# Sensor_Acquisition_Board_Rev1.net
KiCad netlist of a schematic drawn in EAGLE
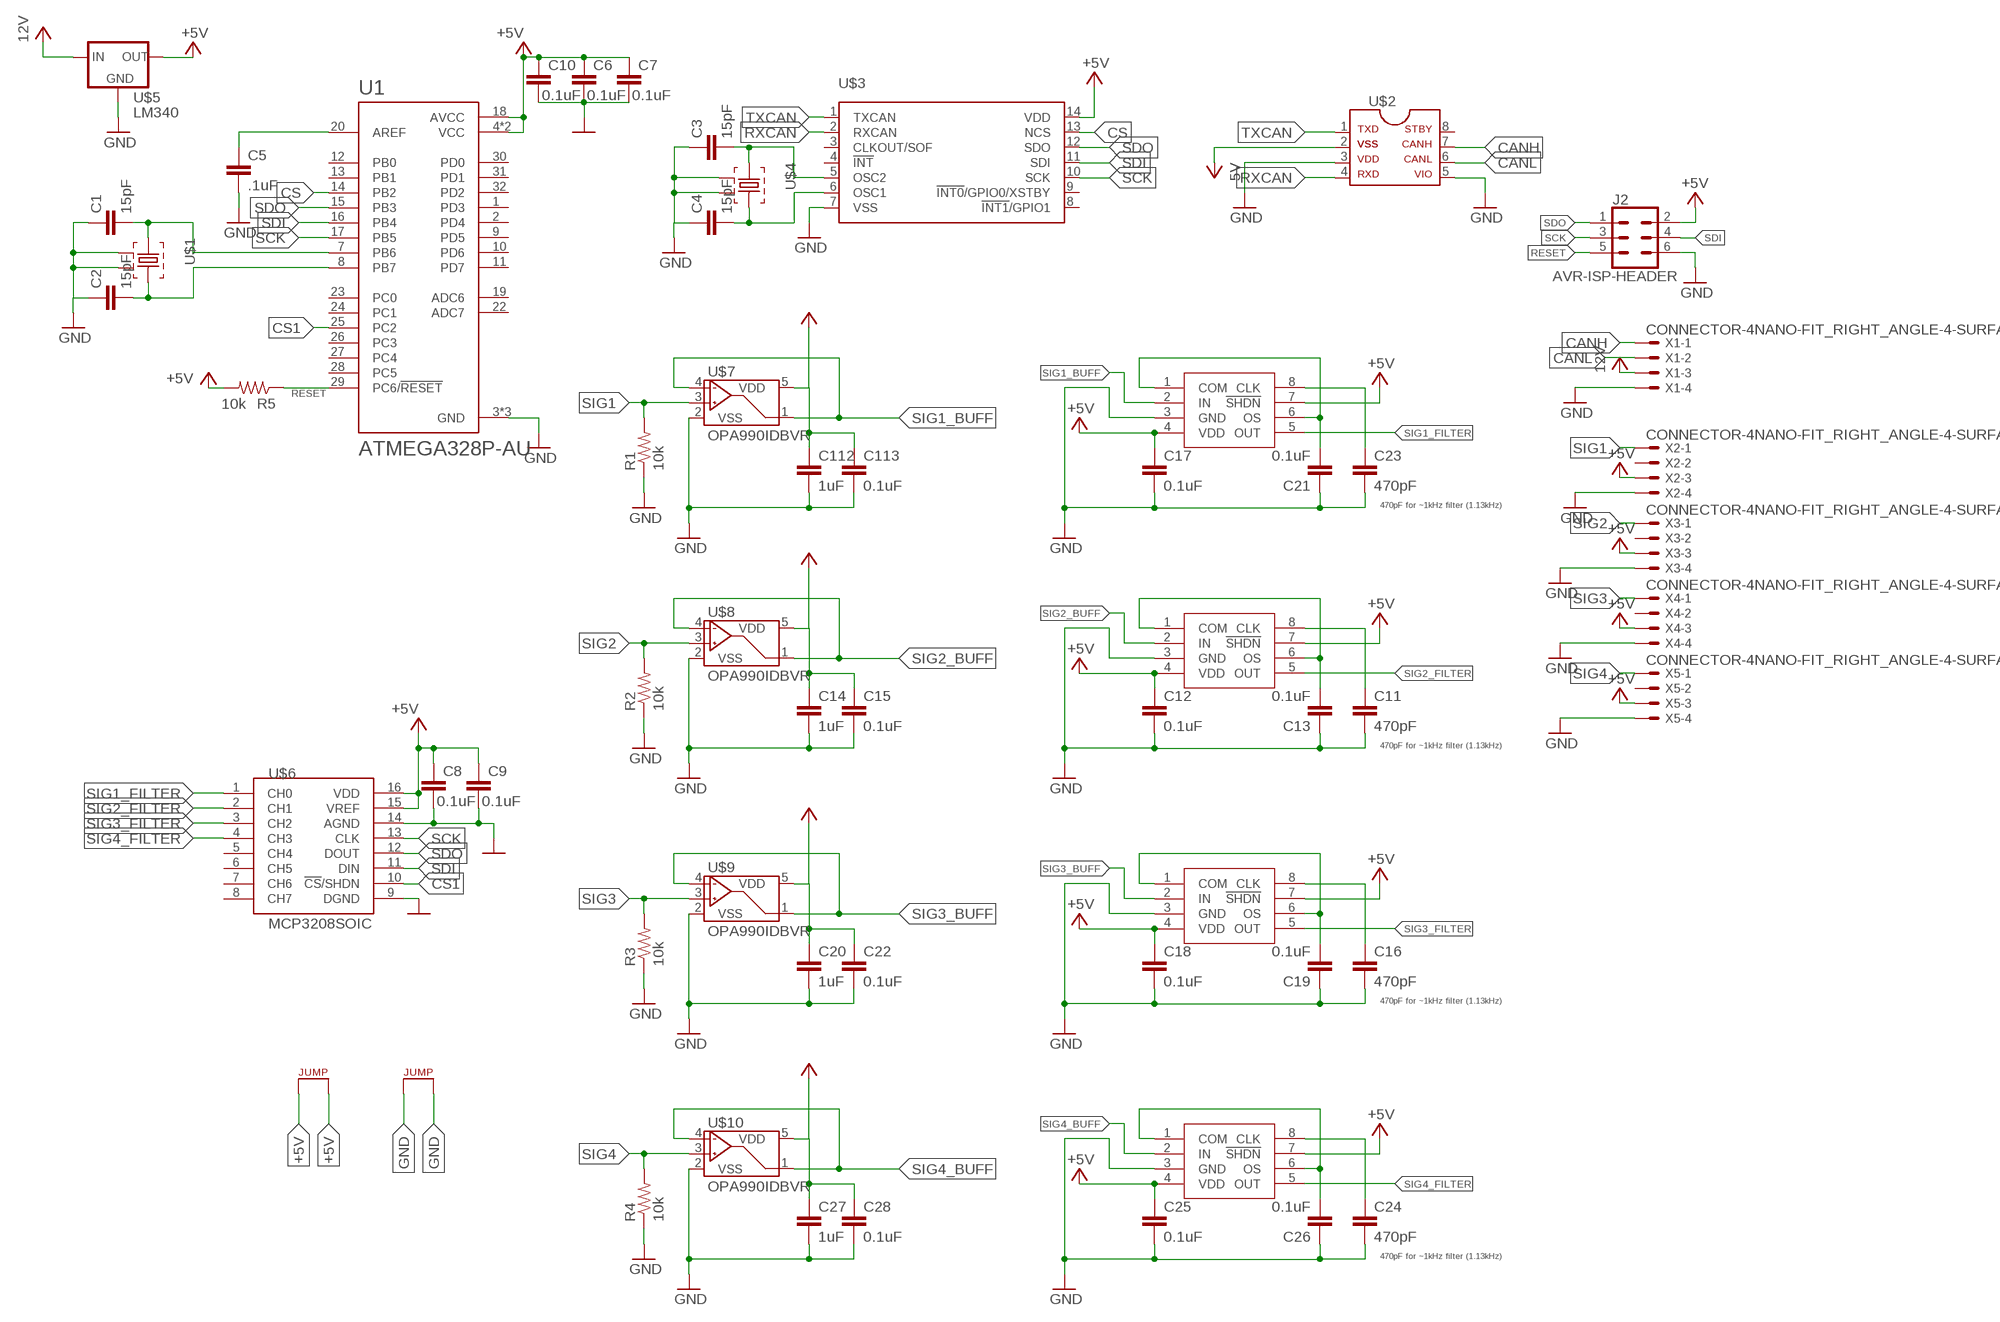
[diagram p0: schematic, sheet 1]

(export (version "E")
  (design (tool "Eeschema 10.0.6"))
  (components
    (comp (ref "C1")
      (value "15pF")
      (footprint "eagle-import:0603-CAP")
      (libsource (lib "eagle-import") (part "CAP0603-CAP"))
    )
    (comp (ref "C2")
      (value "15pF")
      (footprint "eagle-import:0603-CAP")
      (libsource (lib "eagle-import") (part "CAP0603-CAP"))
    )
    (comp (ref "C3")
      (value "15pF")
      (footprint "eagle-import:0603-CAP")
      (libsource (lib "eagle-import") (part "CAP0603-CAP"))
    )
    (comp (ref "C4")
      (value "15pF")
      (footprint "eagle-import:0603-CAP")
      (libsource (lib "eagle-import") (part "CAP0603-CAP"))
    )
    (comp (ref "C5")
      (value ".1uF")
      (footprint "eagle-import:0603-CAP")
      (libsource (lib "eagle-import") (part "CAP0603-CAP"))
    )
    (comp (ref "C6")
      (value "0.1uF")
      (footprint "eagle-import:0603-CAP")
      (libsource (lib "eagle-import") (part "CAP0603-CAP"))
    )
    (comp (ref "C7")
      (value "0.1uF")
      (footprint "eagle-import:0603-CAP")
      (libsource (lib "eagle-import") (part "CAP0603-CAP"))
    )
    (comp (ref "C8")
      (value "0.1uF")
      (footprint "eagle-import:0603-CAP")
      (libsource (lib "eagle-import") (part "CAP0603-CAP"))
    )
    (comp (ref "C9")
      (value "0.1uF")
      (footprint "eagle-import:0603-CAP")
      (libsource (lib "eagle-import") (part "CAP0603-CAP"))
    )
    (comp (ref "C10")
      (value "0.1uF")
      (footprint "eagle-import:0603-CAP")
      (libsource (lib "eagle-import") (part "CAP0603-CAP"))
    )
    (comp (ref "C11")
      (value "470pF")
      (footprint "eagle-import:0603-CAP")
      (libsource (lib "eagle-import") (part "CAP0603-CAP"))
    )
    (comp (ref "C12")
      (value "0.1uF")
      (footprint "eagle-import:0603-CAP")
      (libsource (lib "eagle-import") (part "CAP0603-CAP"))
    )
    (comp (ref "C13")
      (value "0.1uF")
      (footprint "eagle-import:0603-CAP")
      (libsource (lib "eagle-import") (part "CAP0603-CAP"))
    )
    (comp (ref "C14")
      (value "1uF")
      (footprint "eagle-import:0603-CAP")
      (libsource (lib "eagle-import") (part "CAP0603-CAP"))
    )
    (comp (ref "C15")
      (value "0.1uF")
      (footprint "eagle-import:0603-CAP")
      (libsource (lib "eagle-import") (part "CAP0603-CAP"))
    )
    (comp (ref "C16")
      (value "470pF")
      (footprint "eagle-import:0603-CAP")
      (libsource (lib "eagle-import") (part "CAP0603-CAP"))
    )
    (comp (ref "C17")
      (value "0.1uF")
      (footprint "eagle-import:0603-CAP")
      (libsource (lib "eagle-import") (part "CAP0603-CAP"))
    )
    (comp (ref "C18")
      (value "0.1uF")
      (footprint "eagle-import:0603-CAP")
      (libsource (lib "eagle-import") (part "CAP0603-CAP"))
    )
    (comp (ref "C19")
      (value "0.1uF")
      (footprint "eagle-import:0603-CAP")
      (libsource (lib "eagle-import") (part "CAP0603-CAP"))
    )
    (comp (ref "C20")
      (value "1uF")
      (footprint "eagle-import:0603-CAP")
      (libsource (lib "eagle-import") (part "CAP0603-CAP"))
    )
    (comp (ref "C21")
      (value "0.1uF")
      (footprint "eagle-import:0603-CAP")
      (libsource (lib "eagle-import") (part "CAP0603-CAP"))
    )
    (comp (ref "C22")
      (value "0.1uF")
      (footprint "eagle-import:0603-CAP")
      (libsource (lib "eagle-import") (part "CAP0603-CAP"))
    )
    (comp (ref "C23")
      (value "470pF")
      (footprint "eagle-import:0603-CAP")
      (libsource (lib "eagle-import") (part "CAP0603-CAP"))
    )
    (comp (ref "C24")
      (value "470pF")
      (footprint "eagle-import:0603-CAP")
      (libsource (lib "eagle-import") (part "CAP0603-CAP"))
    )
    (comp (ref "C25")
      (value "0.1uF")
      (footprint "eagle-import:0603-CAP")
      (libsource (lib "eagle-import") (part "CAP0603-CAP"))
    )
    (comp (ref "C26")
      (value "0.1uF")
      (footprint "eagle-import:0603-CAP")
      (libsource (lib "eagle-import") (part "CAP0603-CAP"))
    )
    (comp (ref "C27")
      (value "1uF")
      (footprint "eagle-import:0603-CAP")
      (libsource (lib "eagle-import") (part "CAP0603-CAP"))
    )
    (comp (ref "C28")
      (value "0.1uF")
      (footprint "eagle-import:0603-CAP")
      (libsource (lib "eagle-import") (part "CAP0603-CAP"))
    )
    (comp (ref "C112")
      (value "1uF")
      (footprint "eagle-import:0603-CAP")
      (libsource (lib "eagle-import") (part "CAP0603-CAP"))
    )
    (comp (ref "C113")
      (value "0.1uF")
      (footprint "eagle-import:0603-CAP")
      (libsource (lib "eagle-import") (part "CAP0603-CAP"))
    )
    (comp (ref "J1")
      (value "JUMPER.1")
      (footprint "eagle-import:1X02")
      (libsource (lib "eagle-import") (part "JUMPER.1"))
    )
    (comp (ref "J2")
      (value "AVR-ISP-HEADER")
      (footprint "eagle-import:2X03")
      (libsource (lib "eagle-import") (part "AVR-ISP-HEADER"))
    )
    (comp (ref "J3")
      (value "JUMPER.1")
      (footprint "eagle-import:1X02")
      (libsource (lib "eagle-import") (part "JUMPER.1"))
    )
    (comp (ref "R1")
      (value "10k")
      (footprint "eagle-import:0603-RES")
      (libsource (lib "eagle-import") (part "RESISTOR0603"))
    )
    (comp (ref "R2")
      (value "10k")
      (footprint "eagle-import:0603-RES")
      (libsource (lib "eagle-import") (part "RESISTOR0603"))
    )
    (comp (ref "R3")
      (value "10k")
      (footprint "eagle-import:0603-RES")
      (libsource (lib "eagle-import") (part "RESISTOR0603"))
    )
    (comp (ref "R4")
      (value "10k")
      (footprint "eagle-import:0603-RES")
      (libsource (lib "eagle-import") (part "RESISTOR0603"))
    )
    (comp (ref "R5")
      (value "10k")
      (footprint "eagle-import:0603-RES")
      (libsource (lib "eagle-import") (part "RESISTOR0603"))
    )
    (comp (ref "U$1")
      (value "ABM3B")
      (footprint "eagle-import:ABM3B")
      (libsource (lib "eagle-import") (part "ABM3B"))
    )
    (comp (ref "U$2")
      (value "MCP2562FDSOIC-08")
      (footprint "eagle-import:SOIC-08")
      (libsource (lib "eagle-import") (part "MCP2562FDSOIC-08"))
    )
    (comp (ref "U$3")
      (value "MCP2518FD")
      (footprint "eagle-import:SOIC-14")
      (libsource (lib "eagle-import") (part "MCP2518FD"))
    )
    (comp (ref "U$4")
      (value "ABM3B")
      (footprint "eagle-import:ABM3B")
      (libsource (lib "eagle-import") (part "ABM3B"))
    )
    (comp (ref "U$5")
      (value "LM340")
      (footprint "eagle-import:SOT223")
      (libsource (lib "eagle-import") (part "LM340"))
    )
    (comp (ref "U$6")
      (value "MCP3208SOIC")
      (footprint "eagle-import:SOIC-16")
      (libsource (lib "eagle-import") (part "MCP3208SOIC"))
    )
    (comp (ref "U$7")
      (value "OPA990IDBVR")
      (footprint "eagle-import:SOT-23-5")
      (libsource (lib "eagle-import") (part "OPA990IDBVR"))
    )
    (comp (ref "U$8")
      (value "OPA990IDBVR")
      (footprint "eagle-import:SOT-23-5")
      (libsource (lib "eagle-import") (part "OPA990IDBVR"))
    )
    (comp (ref "U$9")
      (value "OPA990IDBVR")
      (footprint "eagle-import:SOT-23-5")
      (libsource (lib "eagle-import") (part "OPA990IDBVR"))
    )
    (comp (ref "U$10")
      (value "OPA990IDBVR")
      (footprint "eagle-import:SOT-23-5")
      (libsource (lib "eagle-import") (part "OPA990IDBVR"))
    )
    (comp (ref "U1")
      (value "ATMEGA328P-AU")
      (footprint "eagle-import:QFP80P900X900X120-32N")
      (fields (field (name "MF") "Microchip"))
      (libsource (lib "eagle-import") (part "ATMEGA328P-AU"))
    )
    (comp (ref "U2")
      (value "MAX7480")
      (footprint "eagle-import:SOIC-08")
      (libsource (lib "eagle-import") (part "MAX7480"))
    )
    (comp (ref "U3")
      (value "MAX7480")
      (footprint "eagle-import:SOIC-08")
      (libsource (lib "eagle-import") (part "MAX7480"))
    )
    (comp (ref "U4")
      (value "MAX7480")
      (footprint "eagle-import:SOIC-08")
      (libsource (lib "eagle-import") (part "MAX7480"))
    )
    (comp (ref "U24")
      (value "MAX7480")
      (footprint "eagle-import:SOIC-08")
      (libsource (lib "eagle-import") (part "MAX7480"))
    )
    (comp (ref "X1")
      (value "CONNECTOR-4NANO-FIT_RIGHT_ANGLE-4-SURFACE")
      (footprint "eagle-import:NANO-FIT_RIGHT_ANGLE-4-SURFACE")
      (libsource (lib "eagle-import") (part "CONNECTOR-4NANO-FIT_RIGHT_ANGLE-4-SURFACE"))
    )
    (comp (ref "X2")
      (value "CONNECTOR-4NANO-FIT_RIGHT_ANGLE-4-SURFACE")
      (footprint "eagle-import:NANO-FIT_RIGHT_ANGLE-4-SURFACE")
      (libsource (lib "eagle-import") (part "CONNECTOR-4NANO-FIT_RIGHT_ANGLE-4-SURFACE"))
    )
    (comp (ref "X3")
      (value "CONNECTOR-4NANO-FIT_RIGHT_ANGLE-4-SURFACE")
      (footprint "eagle-import:NANO-FIT_RIGHT_ANGLE-4-SURFACE")
      (libsource (lib "eagle-import") (part "CONNECTOR-4NANO-FIT_RIGHT_ANGLE-4-SURFACE"))
    )
    (comp (ref "X4")
      (value "CONNECTOR-4NANO-FIT_RIGHT_ANGLE-4-SURFACE")
      (footprint "eagle-import:NANO-FIT_RIGHT_ANGLE-4-SURFACE")
      (libsource (lib "eagle-import") (part "CONNECTOR-4NANO-FIT_RIGHT_ANGLE-4-SURFACE"))
    )
    (comp (ref "X5")
      (value "CONNECTOR-4NANO-FIT_RIGHT_ANGLE-4-SURFACE")
      (footprint "eagle-import:NANO-FIT_RIGHT_ANGLE-4-SURFACE")
      (libsource (lib "eagle-import") (part "CONNECTOR-4NANO-FIT_RIGHT_ANGLE-4-SURFACE"))
    )
  )
  (nets
    (net (code "1") (name "+5V") (class "Default")
      (node (ref "C10") (pin "1") (pinfunction "1_1") (pintype "passive"))
      (node (ref "C112") (pin "1") (pinfunction "1_1") (pintype "passive"))
      (node (ref "C113") (pin "1") (pinfunction "1_1") (pintype "passive"))
      (node (ref "C12") (pin "1") (pinfunction "1_1") (pintype "passive"))
      (node (ref "C14") (pin "1") (pinfunction "1_1") (pintype "passive"))
      (node (ref "C15") (pin "1") (pinfunction "1_1") (pintype "passive"))
      (node (ref "C17") (pin "1") (pinfunction "1_1") (pintype "passive"))
      (node (ref "C18") (pin "1") (pinfunction "1_1") (pintype "passive"))
      (node (ref "C20") (pin "1") (pinfunction "1_1") (pintype "passive"))
      (node (ref "C22") (pin "1") (pinfunction "1_1") (pintype "passive"))
      (node (ref "C25") (pin "1") (pinfunction "1_1") (pintype "passive"))
      (node (ref "C27") (pin "1") (pinfunction "1_1") (pintype "passive"))
      (node (ref "C28") (pin "1") (pinfunction "1_1") (pintype "passive"))
      (node (ref "C6") (pin "1") (pinfunction "1_1") (pintype "passive"))
      (node (ref "C7") (pin "1") (pinfunction "1_1") (pintype "passive"))
      (node (ref "C8") (pin "1") (pinfunction "1_1") (pintype "passive"))
      (node (ref "C9") (pin "1") (pinfunction "1_1") (pintype "passive"))
      (node (ref "J1") (pin "1") (pinfunction "P$1_1") (pintype "bidirectional"))
      (node (ref "J1") (pin "2") (pinfunction "P$2_2") (pintype "bidirectional"))
      (node (ref "J2") (pin "2") (pinfunction "2_2") (pintype "passive"))
      (node (ref "R5") (pin "2") (pinfunction "2_2") (pintype "passive"))
      (node (ref "U$10") (pin "5") (pinfunction "VDD_5") (pintype "passive"))
      (node (ref "U$3") (pin "14") (pinfunction "VDD_14") (pintype "passive"))
      (node (ref "U$5") (pin "3") (pinfunction "OUT_3") (pintype "output"))
      (node (ref "U$6") (pin "15") (pinfunction "VREF_15") (pintype "bidirectional"))
      (node (ref "U$6") (pin "16") (pinfunction "VDD_16") (pintype "bidirectional"))
      (node (ref "U$7") (pin "5") (pinfunction "VDD_5") (pintype "passive"))
      (node (ref "U$8") (pin "5") (pinfunction "VDD_5") (pintype "passive"))
      (node (ref "U$9") (pin "5") (pinfunction "VDD_5") (pintype "passive"))
      (node (ref "U1") (pin "18") (pinfunction "AVCC_18") (pintype "power_in"))
      (node (ref "U1") (pin "4") (pinfunction "VCC_4") (pintype "power_in"))
      (node (ref "U1") (pin "6") (pinfunction "VCC_6") (pintype "power_in"))
      (node (ref "U2") (pin "4") (pinfunction "VDD_4") (pintype "bidirectional"))
      (node (ref "U2") (pin "7") (pinfunction "~{SHDN}_7") (pintype "bidirectional"))
      (node (ref "U24") (pin "4") (pinfunction "VDD_4") (pintype "bidirectional"))
      (node (ref "U24") (pin "7") (pinfunction "~{SHDN}_7") (pintype "bidirectional"))
      (node (ref "U3") (pin "4") (pinfunction "VDD_4") (pintype "bidirectional"))
      (node (ref "U3") (pin "7") (pinfunction "~{SHDN}_7") (pintype "bidirectional"))
      (node (ref "U4") (pin "4") (pinfunction "VDD_4") (pintype "bidirectional"))
      (node (ref "U4") (pin "7") (pinfunction "~{SHDN}_7") (pintype "bidirectional"))
      (node (ref "X2") (pin "3") (pinfunction "S_3") (pintype "passive"))
      (node (ref "X3") (pin "3") (pinfunction "S_3") (pintype "passive"))
      (node (ref "X4") (pin "3") (pinfunction "S_3") (pintype "passive"))
      (node (ref "X5") (pin "3") (pinfunction "S_3") (pintype "passive"))
    )
    (net (code "2") (name "12V") (class "Default")
      (node (ref "U$2") (pin "2") (pinfunction "2_2") (pintype "passive"))
      (node (ref "U$5") (pin "1") (pinfunction "IN_1") (pintype "input"))
      (node (ref "X1") (pin "3") (pinfunction "S_3") (pintype "passive"))
    )
    (net (code "3") (name "CANH") (class "Default")
      (node (ref "U$2") (pin "7") (pinfunction "7_7") (pintype "passive"))
      (node (ref "X1") (pin "1") (pinfunction "S_1") (pintype "passive"))
    )
    (net (code "4") (name "CANL") (class "Default")
      (node (ref "U$2") (pin "6") (pinfunction "6_6") (pintype "passive"))
      (node (ref "X1") (pin "2") (pinfunction "S_2") (pintype "passive"))
    )
    (net (code "5") (name "CS") (class "Default")
      (node (ref "U$3") (pin "13") (pinfunction "NCS_13") (pintype "passive"))
      (node (ref "U1") (pin "14") (pinfunction "PB2_14") (pintype "bidirectional"))
    )
    (net (code "6") (name "CS1") (class "Default")
      (node (ref "U$6") (pin "10") (pinfunction "~{CS}/SHDN_10") (pintype "bidirectional"))
      (node (ref "U1") (pin "25") (pinfunction "PC2_25") (pintype "bidirectional"))
    )
    (net (code "7") (name "GND") (class "Default")
      (node (ref "C1") (pin "1") (pinfunction "1_1") (pintype "passive"))
      (node (ref "C10") (pin "2") (pinfunction "2_2") (pintype "passive"))
      (node (ref "C11") (pin "2") (pinfunction "2_2") (pintype "passive"))
      (node (ref "C112") (pin "2") (pinfunction "2_2") (pintype "passive"))
      (node (ref "C113") (pin "2") (pinfunction "2_2") (pintype "passive"))
      (node (ref "C12") (pin "2") (pinfunction "2_2") (pintype "passive"))
      (node (ref "C13") (pin "1") (pinfunction "1_1") (pintype "passive"))
      (node (ref "C14") (pin "2") (pinfunction "2_2") (pintype "passive"))
      (node (ref "C15") (pin "2") (pinfunction "2_2") (pintype "passive"))
      (node (ref "C16") (pin "2") (pinfunction "2_2") (pintype "passive"))
      (node (ref "C17") (pin "2") (pinfunction "2_2") (pintype "passive"))
      (node (ref "C18") (pin "2") (pinfunction "2_2") (pintype "passive"))
      (node (ref "C19") (pin "1") (pinfunction "1_1") (pintype "passive"))
      (node (ref "C2") (pin "1") (pinfunction "1_1") (pintype "passive"))
      (node (ref "C20") (pin "2") (pinfunction "2_2") (pintype "passive"))
      (node (ref "C21") (pin "1") (pinfunction "1_1") (pintype "passive"))
      (node (ref "C22") (pin "2") (pinfunction "2_2") (pintype "passive"))
      (node (ref "C23") (pin "2") (pinfunction "2_2") (pintype "passive"))
      (node (ref "C24") (pin "2") (pinfunction "2_2") (pintype "passive"))
      (node (ref "C25") (pin "2") (pinfunction "2_2") (pintype "passive"))
      (node (ref "C26") (pin "1") (pinfunction "1_1") (pintype "passive"))
      (node (ref "C27") (pin "2") (pinfunction "2_2") (pintype "passive"))
      (node (ref "C28") (pin "2") (pinfunction "2_2") (pintype "passive"))
      (node (ref "C3") (pin "1") (pinfunction "1_1") (pintype "passive"))
      (node (ref "C4") (pin "1") (pinfunction "1_1") (pintype "passive"))
      (node (ref "C5") (pin "2") (pinfunction "2_2") (pintype "passive"))
      (node (ref "C6") (pin "2") (pinfunction "2_2") (pintype "passive"))
      (node (ref "C7") (pin "2") (pinfunction "2_2") (pintype "passive"))
      (node (ref "C8") (pin "2") (pinfunction "2_2") (pintype "passive"))
      (node (ref "C9") (pin "2") (pinfunction "2_2") (pintype "passive"))
      (node (ref "J2") (pin "6") (pinfunction "6_6") (pintype "passive"))
      (node (ref "J3") (pin "1") (pinfunction "P$1_1") (pintype "bidirectional"))
      (node (ref "J3") (pin "2") (pinfunction "P$2_2") (pintype "bidirectional"))
      (node (ref "R1") (pin "1") (pinfunction "1_1") (pintype "passive"))
      (node (ref "R2") (pin "1") (pinfunction "1_1") (pintype "passive"))
      (node (ref "R3") (pin "1") (pinfunction "1_1") (pintype "passive"))
      (node (ref "R4") (pin "1") (pinfunction "1_1") (pintype "passive"))
      (node (ref "U$1") (pin "GND") (pinfunction "GND_GND") (pintype "passive"))
      (node (ref "U$1") (pin "GND2") (pinfunction "GND2_GND2") (pintype "passive"))
      (node (ref "U$10") (pin "2") (pinfunction "VSS_2") (pintype "passive"))
      (node (ref "U$2") (pin "3") (pinfunction "3_3") (pintype "passive"))
      (node (ref "U$2") (pin "5") (pinfunction "5_5") (pintype "passive"))
      (node (ref "U$3") (pin "7") (pinfunction "VSS_7") (pintype "passive"))
      (node (ref "U$4") (pin "GND") (pinfunction "GND_GND") (pintype "passive"))
      (node (ref "U$4") (pin "GND2") (pinfunction "GND2_GND2") (pintype "passive"))
      (node (ref "U$5") (pin "2") (pinfunction "GND_2") (pintype "input"))
      (node (ref "U$5") (pin "4") (pinfunction "GND_4") (pintype "input"))
      (node (ref "U$6") (pin "14") (pinfunction "AGND_14") (pintype "bidirectional"))
      (node (ref "U$6") (pin "9") (pinfunction "DGND_9") (pintype "bidirectional"))
      (node (ref "U$7") (pin "2") (pinfunction "VSS_2") (pintype "passive"))
      (node (ref "U$8") (pin "2") (pinfunction "VSS_2") (pintype "passive"))
      (node (ref "U$9") (pin "2") (pinfunction "VSS_2") (pintype "passive"))
      (node (ref "U1") (pin "21") (pinfunction "GND_21") (pintype "power_in"))
      (node (ref "U1") (pin "3") (pinfunction "GND_3") (pintype "power_in"))
      (node (ref "U1") (pin "5") (pinfunction "GND_5") (pintype "power_in"))
      (node (ref "U2") (pin "3") (pinfunction "GND_3") (pintype "bidirectional"))
      (node (ref "U24") (pin "3") (pinfunction "GND_3") (pintype "bidirectional"))
      (node (ref "U3") (pin "3") (pinfunction "GND_3") (pintype "bidirectional"))
      (node (ref "U4") (pin "3") (pinfunction "GND_3") (pintype "bidirectional"))
      (node (ref "X1") (pin "4") (pinfunction "S_4") (pintype "passive"))
      (node (ref "X2") (pin "4") (pinfunction "S_4") (pintype "passive"))
      (node (ref "X3") (pin "4") (pinfunction "S_4") (pintype "passive"))
      (node (ref "X4") (pin "4") (pinfunction "S_4") (pintype "passive"))
      (node (ref "X5") (pin "4") (pinfunction "S_4") (pintype "passive"))
    )
    (net (code "8") (name "Net-(U$3-OSC1)") (class "Default")
      (node (ref "C4") (pin "2") (pinfunction "2_2") (pintype "passive"))
      (node (ref "U$3") (pin "6") (pinfunction "OSC1_6") (pintype "passive"))
      (node (ref "U$4") (pin "3") (pinfunction "3_3") (pintype "passive"))
    )
    (net (code "9") (name "Net-(U$3-OSC2)") (class "Default")
      (node (ref "C3") (pin "2") (pinfunction "2_2") (pintype "passive"))
      (node (ref "U$3") (pin "5") (pinfunction "OSC2_5") (pintype "passive"))
      (node (ref "U$4") (pin "1") (pinfunction "1_1") (pintype "passive"))
    )
    (net (code "10") (name "Net-(U1-AREF)") (class "Default")
      (node (ref "C5") (pin "1") (pinfunction "1_1") (pintype "passive"))
      (node (ref "U1") (pin "20") (pinfunction "AREF_20") (pintype "input"))
    )
    (net (code "11") (name "Net-(U1-PB6)") (class "Default")
      (node (ref "C1") (pin "2") (pinfunction "2_2") (pintype "passive"))
      (node (ref "U$1") (pin "1") (pinfunction "1_1") (pintype "passive"))
      (node (ref "U1") (pin "7") (pinfunction "PB6_7") (pintype "bidirectional"))
    )
    (net (code "12") (name "Net-(U1-PB7)") (class "Default")
      (node (ref "C2") (pin "2") (pinfunction "2_2") (pintype "passive"))
      (node (ref "U$1") (pin "3") (pinfunction "3_3") (pintype "passive"))
      (node (ref "U1") (pin "8") (pinfunction "PB7_8") (pintype "bidirectional"))
    )
    (net (code "13") (name "Net-(U2-CLK)") (class "Default")
      (node (ref "C11") (pin "1") (pinfunction "1_1") (pintype "passive"))
      (node (ref "U2") (pin "8") (pinfunction "CLK_8") (pintype "bidirectional"))
    )
    (net (code "14") (name "Net-(U2-COM)") (class "Default")
      (node (ref "C13") (pin "2") (pinfunction "2_2") (pintype "passive"))
      (node (ref "U2") (pin "1") (pinfunction "COM_1") (pintype "bidirectional"))
      (node (ref "U2") (pin "6") (pinfunction "OS_6") (pintype "bidirectional"))
    )
    (net (code "15") (name "Net-(U3-CLK)") (class "Default")
      (node (ref "C16") (pin "1") (pinfunction "1_1") (pintype "passive"))
      (node (ref "U3") (pin "8") (pinfunction "CLK_8") (pintype "bidirectional"))
    )
    (net (code "16") (name "Net-(U3-COM)") (class "Default")
      (node (ref "C19") (pin "2") (pinfunction "2_2") (pintype "passive"))
      (node (ref "U3") (pin "1") (pinfunction "COM_1") (pintype "bidirectional"))
      (node (ref "U3") (pin "6") (pinfunction "OS_6") (pintype "bidirectional"))
    )
    (net (code "17") (name "Net-(U4-CLK)") (class "Default")
      (node (ref "C24") (pin "1") (pinfunction "1_1") (pintype "passive"))
      (node (ref "U4") (pin "8") (pinfunction "CLK_8") (pintype "bidirectional"))
    )
    (net (code "18") (name "Net-(U4-COM)") (class "Default")
      (node (ref "C26") (pin "2") (pinfunction "2_2") (pintype "passive"))
      (node (ref "U4") (pin "1") (pinfunction "COM_1") (pintype "bidirectional"))
      (node (ref "U4") (pin "6") (pinfunction "OS_6") (pintype "bidirectional"))
    )
    (net (code "19") (name "Net-(U24-CLK)") (class "Default")
      (node (ref "C23") (pin "1") (pinfunction "1_1") (pintype "passive"))
      (node (ref "U24") (pin "8") (pinfunction "CLK_8") (pintype "bidirectional"))
    )
    (net (code "20") (name "Net-(U24-COM)") (class "Default")
      (node (ref "C21") (pin "2") (pinfunction "2_2") (pintype "passive"))
      (node (ref "U24") (pin "1") (pinfunction "COM_1") (pintype "bidirectional"))
      (node (ref "U24") (pin "6") (pinfunction "OS_6") (pintype "bidirectional"))
    )
    (net (code "21") (name "RESET") (class "Default")
      (node (ref "J2") (pin "5") (pinfunction "5_5") (pintype "passive"))
      (node (ref "R5") (pin "1") (pinfunction "1_1") (pintype "passive"))
      (node (ref "U1") (pin "29") (pinfunction "PC6/~{RESET}_29") (pintype "bidirectional"))
    )
    (net (code "22") (name "RXCAN") (class "Default")
      (node (ref "U$2") (pin "4") (pinfunction "4_4") (pintype "passive"))
      (node (ref "U$3") (pin "2") (pinfunction "RXCAN_2") (pintype "passive"))
    )
    (net (code "23") (name "SCK") (class "Default")
      (node (ref "J2") (pin "3") (pinfunction "3_3") (pintype "passive"))
      (node (ref "U$3") (pin "10") (pinfunction "SCK_10") (pintype "passive"))
      (node (ref "U$6") (pin "13") (pinfunction "CLK_13") (pintype "bidirectional"))
      (node (ref "U1") (pin "17") (pinfunction "PB5_17") (pintype "bidirectional"))
    )
    (net (code "24") (name "SDI") (class "Default")
      (node (ref "J2") (pin "4") (pinfunction "4_4") (pintype "passive"))
      (node (ref "U$3") (pin "11") (pinfunction "SDI_11") (pintype "passive"))
      (node (ref "U$6") (pin "11") (pinfunction "DIN_11") (pintype "bidirectional"))
      (node (ref "U1") (pin "16") (pinfunction "PB4_16") (pintype "bidirectional"))
    )
    (net (code "25") (name "SDO") (class "Default")
      (node (ref "J2") (pin "1") (pinfunction "1_1") (pintype "passive"))
      (node (ref "U$3") (pin "12") (pinfunction "SDO_12") (pintype "passive"))
      (node (ref "U$6") (pin "12") (pinfunction "DOUT_12") (pintype "bidirectional"))
      (node (ref "U1") (pin "15") (pinfunction "PB3_15") (pintype "bidirectional"))
    )
    (net (code "26") (name "SIG1") (class "Default")
      (node (ref "R1") (pin "2") (pinfunction "2_2") (pintype "passive"))
      (node (ref "U$7") (pin "3") (pinfunction "VIN+_3") (pintype "passive"))
      (node (ref "X2") (pin "1") (pinfunction "S_1") (pintype "passive"))
    )
    (net (code "27") (name "SIG1_BUFF") (class "Default")
      (node (ref "U$7") (pin "1") (pinfunction "VOUT_1") (pintype "passive"))
      (node (ref "U$7") (pin "4") (pinfunction "VIN-_4") (pintype "passive"))
      (node (ref "U24") (pin "2") (pinfunction "IN_2") (pintype "bidirectional"))
    )
    (net (code "28") (name "SIG1_FILTER") (class "Default")
      (node (ref "U$6") (pin "1") (pinfunction "CH0_1") (pintype "bidirectional"))
      (node (ref "U24") (pin "5") (pinfunction "OUT_5") (pintype "bidirectional"))
    )
    (net (code "29") (name "SIG2") (class "Default")
      (node (ref "R2") (pin "2") (pinfunction "2_2") (pintype "passive"))
      (node (ref "U$8") (pin "3") (pinfunction "VIN+_3") (pintype "passive"))
      (node (ref "X3") (pin "1") (pinfunction "S_1") (pintype "passive"))
    )
    (net (code "30") (name "SIG2_BUFF") (class "Default")
      (node (ref "U$8") (pin "1") (pinfunction "VOUT_1") (pintype "passive"))
      (node (ref "U$8") (pin "4") (pinfunction "VIN-_4") (pintype "passive"))
      (node (ref "U2") (pin "2") (pinfunction "IN_2") (pintype "bidirectional"))
    )
    (net (code "31") (name "SIG2_FILTER") (class "Default")
      (node (ref "U$6") (pin "2") (pinfunction "CH1_2") (pintype "bidirectional"))
      (node (ref "U2") (pin "5") (pinfunction "OUT_5") (pintype "bidirectional"))
    )
    (net (code "32") (name "SIG3") (class "Default")
      (node (ref "R3") (pin "2") (pinfunction "2_2") (pintype "passive"))
      (node (ref "U$9") (pin "3") (pinfunction "VIN+_3") (pintype "passive"))
      (node (ref "X4") (pin "1") (pinfunction "S_1") (pintype "passive"))
    )
    (net (code "33") (name "SIG3_BUFF") (class "Default")
      (node (ref "U$9") (pin "1") (pinfunction "VOUT_1") (pintype "passive"))
      (node (ref "U$9") (pin "4") (pinfunction "VIN-_4") (pintype "passive"))
      (node (ref "U3") (pin "2") (pinfunction "IN_2") (pintype "bidirectional"))
    )
    (net (code "34") (name "SIG3_FILTER") (class "Default")
      (node (ref "U$6") (pin "3") (pinfunction "CH2_3") (pintype "bidirectional"))
      (node (ref "U3") (pin "5") (pinfunction "OUT_5") (pintype "bidirectional"))
    )
    (net (code "35") (name "SIG4") (class "Default")
      (node (ref "R4") (pin "2") (pinfunction "2_2") (pintype "passive"))
      (node (ref "U$10") (pin "3") (pinfunction "VIN+_3") (pintype "passive"))
      (node (ref "X5") (pin "1") (pinfunction "S_1") (pintype "passive"))
    )
    (net (code "36") (name "SIG4_BUFF") (class "Default")
      (node (ref "U$10") (pin "1") (pinfunction "VOUT_1") (pintype "passive"))
      (node (ref "U$10") (pin "4") (pinfunction "VIN-_4") (pintype "passive"))
      (node (ref "U4") (pin "2") (pinfunction "IN_2") (pintype "bidirectional"))
    )
    (net (code "37") (name "SIG4_FILTER") (class "Default")
      (node (ref "U$6") (pin "4") (pinfunction "CH3_4") (pintype "bidirectional"))
      (node (ref "U4") (pin "5") (pinfunction "OUT_5") (pintype "bidirectional"))
    )
    (net (code "38") (name "TXCAN") (class "Default")
      (node (ref "U$2") (pin "1") (pinfunction "1_1") (pintype "passive"))
      (node (ref "U$3") (pin "1") (pinfunction "TXCAN_1") (pintype "passive"))
    )
    (net (code "39") (name "unconnected-(U$2-Pad8)") (class "Default")
      (node (ref "U$2") (pin "8") (pinfunction "8_8") (pintype "passive"))
    )
    (net (code "40") (name "unconnected-(U$3-CLKOUT{slash}SOF-Pad3)") (class "Default")
      (node (ref "U$3") (pin "3") (pinfunction "CLKOUT/SOF_3") (pintype "passive"))
    )
    (net (code "41") (name "unconnected-(U$3-~{INT0}{slash}GPIO0{slash}XSTBY-Pad9)") (class "Default")
      (node (ref "U$3") (pin "9") (pinfunction "~{INT0}/GPIO0/XSTBY_9") (pintype "passive"))
    )
    (net (code "42") (name "unconnected-(U$3-~{INT1}{slash}GPIO1-Pad8)") (class "Default")
      (node (ref "U$3") (pin "8") (pinfunction "~{INT1}/GPIO1_8") (pintype "passive"))
    )
    (net (code "43") (name "unconnected-(U$3-~{INT}-Pad4)") (class "Default")
      (node (ref "U$3") (pin "4") (pinfunction "~{INT}_4") (pintype "passive"))
    )
    (net (code "44") (name "unconnected-(U$6-CH4-Pad5)") (class "Default")
      (node (ref "U$6") (pin "5") (pinfunction "CH4_5") (pintype "bidirectional"))
    )
    (net (code "45") (name "unconnected-(U$6-CH5-Pad6)") (class "Default")
      (node (ref "U$6") (pin "6") (pinfunction "CH5_6") (pintype "bidirectional"))
    )
    (net (code "46") (name "unconnected-(U$6-CH6-Pad7)") (class "Default")
      (node (ref "U$6") (pin "7") (pinfunction "CH6_7") (pintype "bidirectional"))
    )
    (net (code "47") (name "unconnected-(U$6-CH7-Pad8)") (class "Default")
      (node (ref "U$6") (pin "8") (pinfunction "CH7_8") (pintype "bidirectional"))
    )
    (net (code "48") (name "unconnected-(U1-ADC6-Pad19)") (class "Default")
      (node (ref "U1") (pin "19") (pinfunction "ADC6_19") (pintype "bidirectional"))
    )
    (net (code "49") (name "unconnected-(U1-ADC7-Pad22)") (class "Default")
      (node (ref "U1") (pin "22") (pinfunction "ADC7_22") (pintype "bidirectional"))
    )
    (net (code "50") (name "unconnected-(U1-PB0-Pad12)") (class "Default")
      (node (ref "U1") (pin "12") (pinfunction "PB0_12") (pintype "bidirectional"))
    )
    (net (code "51") (name "unconnected-(U1-PB1-Pad13)") (class "Default")
      (node (ref "U1") (pin "13") (pinfunction "PB1_13") (pintype "bidirectional"))
    )
    (net (code "52") (name "unconnected-(U1-PC0-Pad23)") (class "Default")
      (node (ref "U1") (pin "23") (pinfunction "PC0_23") (pintype "bidirectional"))
    )
    (net (code "53") (name "unconnected-(U1-PC1-Pad24)") (class "Default")
      (node (ref "U1") (pin "24") (pinfunction "PC1_24") (pintype "bidirectional"))
    )
    (net (code "54") (name "unconnected-(U1-PC3-Pad26)") (class "Default")
      (node (ref "U1") (pin "26") (pinfunction "PC3_26") (pintype "bidirectional"))
    )
    (net (code "55") (name "unconnected-(U1-PC4-Pad27)") (class "Default")
      (node (ref "U1") (pin "27") (pinfunction "PC4_27") (pintype "bidirectional"))
    )
    (net (code "56") (name "unconnected-(U1-PC5-Pad28)") (class "Default")
      (node (ref "U1") (pin "28") (pinfunction "PC5_28") (pintype "bidirectional"))
    )
    (net (code "57") (name "unconnected-(U1-PD0-Pad30)") (class "Default")
      (node (ref "U1") (pin "30") (pinfunction "PD0_30") (pintype "bidirectional"))
    )
    (net (code "58") (name "unconnected-(U1-PD1-Pad31)") (class "Default")
      (node (ref "U1") (pin "31") (pinfunction "PD1_31") (pintype "bidirectional"))
    )
    (net (code "59") (name "unconnected-(U1-PD2-Pad32)") (class "Default")
      (node (ref "U1") (pin "32") (pinfunction "PD2_32") (pintype "bidirectional"))
    )
    (net (code "60") (name "unconnected-(U1-PD3-Pad1)") (class "Default")
      (node (ref "U1") (pin "1") (pinfunction "PD3_1") (pintype "bidirectional"))
    )
    (net (code "61") (name "unconnected-(U1-PD4-Pad2)") (class "Default")
      (node (ref "U1") (pin "2") (pinfunction "PD4_2") (pintype "bidirectional"))
    )
    (net (code "62") (name "unconnected-(U1-PD5-Pad9)") (class "Default")
      (node (ref "U1") (pin "9") (pinfunction "PD5_9") (pintype "bidirectional"))
    )
    (net (code "63") (name "unconnected-(U1-PD6-Pad10)") (class "Default")
      (node (ref "U1") (pin "10") (pinfunction "PD6_10") (pintype "bidirectional"))
    )
    (net (code "64") (name "unconnected-(U1-PD7-Pad11)") (class "Default")
      (node (ref "U1") (pin "11") (pinfunction "PD7_11") (pintype "bidirectional"))
    )
    (net (code "65") (name "unconnected-(X2B-S-Pad2)") (class "Default")
      (node (ref "X2") (pin "2") (pinfunction "S_2") (pintype "passive"))
    )
    (net (code "66") (name "unconnected-(X3B-S-Pad2)") (class "Default")
      (node (ref "X3") (pin "2") (pinfunction "S_2") (pintype "passive"))
    )
    (net (code "67") (name "unconnected-(X4B-S-Pad2)") (class "Default")
      (node (ref "X4") (pin "2") (pinfunction "S_2") (pintype "passive"))
    )
    (net (code "68") (name "unconnected-(X5B-S-Pad2)") (class "Default")
      (node (ref "X5") (pin "2") (pinfunction "S_2") (pintype "passive"))
    )
  )
)
